# MagEnc.net
KiCad netlist of a schematic drawn in EAGLE
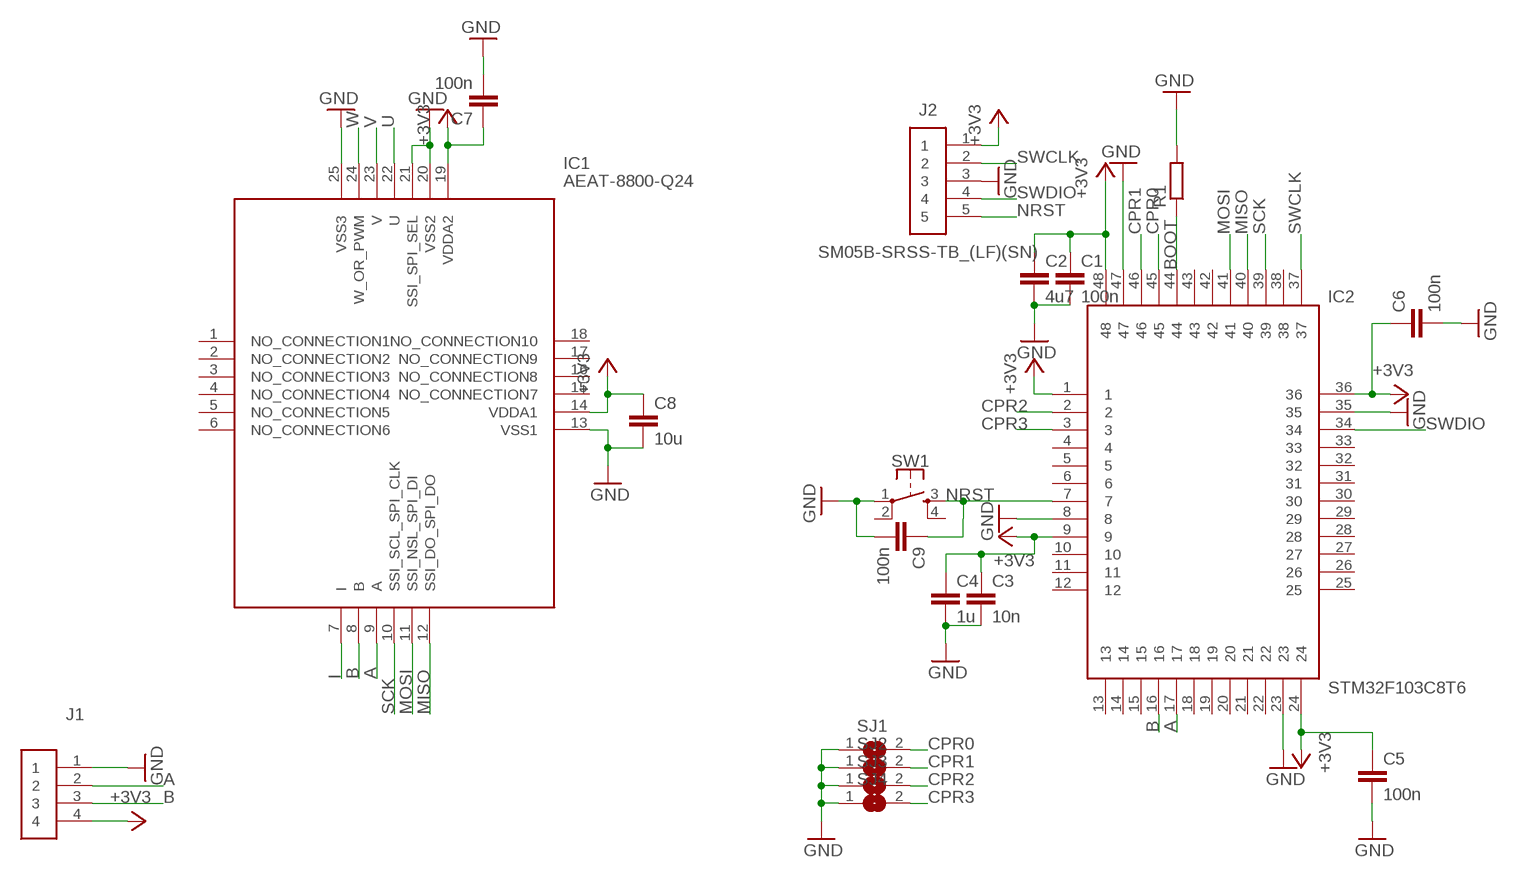
[diagram p0: schematic, sheet 1]

(export (version "E")
  (design (tool "Eeschema 10.0.6"))
  (components
    (comp (ref "C1")
      (value "100n")
      (footprint "eagle-import:C0402K")
      (libsource (lib "eagle-import") (part "C-EUC0402K"))
    )
    (comp (ref "C2")
      (value "4u7")
      (footprint "eagle-import:C0603K")
      (libsource (lib "eagle-import") (part "C-EUC0603K"))
    )
    (comp (ref "C3")
      (value "10n")
      (footprint "eagle-import:C0402K")
      (libsource (lib "eagle-import") (part "C-EUC0402K"))
    )
    (comp (ref "C4")
      (value "1u")
      (footprint "eagle-import:C0603K")
      (libsource (lib "eagle-import") (part "C-EUC0603K"))
    )
    (comp (ref "C5")
      (value "100n")
      (footprint "eagle-import:C0402K")
      (libsource (lib "eagle-import") (part "C-EUC0402K"))
    )
    (comp (ref "C6")
      (value "100n")
      (footprint "eagle-import:C0402K")
      (libsource (lib "eagle-import") (part "C-EUC0402K"))
    )
    (comp (ref "C7")
      (value "100n")
      (footprint "eagle-import:C0402K")
      (libsource (lib "eagle-import") (part "C-EUC0402K"))
    )
    (comp (ref "C8")
      (value "10u")
      (footprint "eagle-import:C0603K")
      (libsource (lib "eagle-import") (part "C-EUC0603K"))
    )
    (comp (ref "C9")
      (value "100n")
      (footprint "eagle-import:C0402K")
      (libsource (lib "eagle-import") (part "C-EUC0402K"))
    )
    (comp (ref "IC1")
      (value "AEAT-8800-Q24")
      (footprint "eagle-import:QFN65P500X500X90-25N")
      (libsource (lib "eagle-import") (part "AEAT-8800-Q24"))
    )
    (comp (ref "IC2")
      (value "STM32F103C8T6")
      (footprint "eagle-import:QFP50P900X900X160-48N")
      (libsource (lib "eagle-import") (part "STM32_LQFP48_7X7"))
    )
    (comp (ref "J1")
      (value "DF65-4P-1.7V(21)")
      (footprint "eagle-import:DF654P17V21")
      (fields (field (name "RS_PART_NUMBER") "8735161P"))
      (libsource (lib "eagle-import") (part "DF65-4P-1.7V(21)"))
    )
    (comp (ref "J2")
      (value "SM05B-SRSS-TB_(LF)(SN)")
      (footprint "eagle-import:SM05B-SRSS-TB")
      (fields (field (name "MANUFACTURER_PART_NUMBER") "SM05B-SRSS-TB(LF)(SN)"))
      (libsource (lib "eagle-import") (part "SM05B-SRSS-TB_(LF)(SN)"))
    )
    (comp (ref "R1")
      (value "R-EU_R0402")
      (footprint "eagle-import:R0402")
      (libsource (lib "eagle-import") (part "R-EU_R0402"))
    )
    (comp (ref "SJ1") (value "SJ") (footprint "eagle-import:SJ") (libsource (lib "eagle-import") (part "SJ")))
    (comp (ref "SJ2") (value "SJ") (footprint "eagle-import:SJ") (libsource (lib "eagle-import") (part "SJ")))
    (comp (ref "SJ3") (value "SJ") (footprint "eagle-import:SJ") (libsource (lib "eagle-import") (part "SJ")))
    (comp (ref "SJ4") (value "SJ") (footprint "eagle-import:SJ") (libsource (lib "eagle-import") (part "SJ")))
    (comp (ref "SW1")
      (value "SKRPACE010")
      (footprint "eagle-import:SMT(4.2X3.2)")
      (libsource (lib "eagle-import") (part "SKRPACE010"))
    )
  )
  (nets
    (net (code "1") (name "+3V3") (class "Default")
      (node (ref "C1") (pin "1") (pinfunction "1_1") (pintype "passive"))
      (node (ref "C2") (pin "1") (pinfunction "1_1") (pintype "passive"))
      (node (ref "C3") (pin "1") (pinfunction "1_1") (pintype "passive"))
      (node (ref "C4") (pin "1") (pinfunction "1_1") (pintype "passive"))
      (node (ref "C5") (pin "1") (pinfunction "1_1") (pintype "passive"))
      (node (ref "C6") (pin "1") (pinfunction "1_1") (pintype "passive"))
      (node (ref "C7") (pin "1") (pinfunction "1_1") (pintype "passive"))
      (node (ref "C8") (pin "1") (pinfunction "1_1") (pintype "passive"))
      (node (ref "IC1") (pin "14") (pinfunction "VDDA1_14") (pintype "bidirectional"))
      (node (ref "IC1") (pin "19") (pinfunction "VDDA2_19") (pintype "bidirectional"))
      (node (ref "IC2") (pin "1") (pinfunction "1_1") (pintype "bidirectional"))
      (node (ref "IC2") (pin "24") (pinfunction "24_24") (pintype "bidirectional"))
      (node (ref "IC2") (pin "36") (pinfunction "36_36") (pintype "bidirectional"))
      (node (ref "IC2") (pin "48") (pinfunction "48_48") (pintype "bidirectional"))
      (node (ref "IC2") (pin "9") (pinfunction "9_9") (pintype "bidirectional"))
      (node (ref "J1") (pin "4") (pinfunction "4_4") (pintype "input"))
      (node (ref "J2") (pin "1") (pinfunction "1_1") (pintype "passive"))
    )
    (net (code "2") (name "/A") (class "Default")
      (node (ref "IC1") (pin "9") (pinfunction "A_9") (pintype "bidirectional"))
      (node (ref "IC2") (pin "17") (pinfunction "17_17") (pintype "bidirectional"))
      (node (ref "J1") (pin "2") (pinfunction "2_2") (pintype "input"))
    )
    (net (code "3") (name "/B") (class "Default")
      (node (ref "IC1") (pin "8") (pinfunction "B_8") (pintype "bidirectional"))
      (node (ref "IC2") (pin "16") (pinfunction "16_16") (pintype "bidirectional"))
      (node (ref "J1") (pin "3") (pinfunction "3_3") (pintype "input"))
    )
    (net (code "4") (name "/BOOT") (class "Default")
      (node (ref "IC2") (pin "44") (pinfunction "44_44") (pintype "bidirectional"))
      (node (ref "R1") (pin "1") (pinfunction "1_1") (pintype "passive"))
    )
    (net (code "5") (name "/CPR0") (class "Default")
      (node (ref "IC2") (pin "45") (pinfunction "45_45") (pintype "bidirectional"))
      (node (ref "SJ1") (pin "2") (pinfunction "2_2") (pintype "passive"))
    )
    (net (code "6") (name "/CPR1") (class "Default")
      (node (ref "IC2") (pin "46") (pinfunction "46_46") (pintype "bidirectional"))
      (node (ref "SJ2") (pin "2") (pinfunction "2_2") (pintype "passive"))
    )
    (net (code "7") (name "/CPR2") (class "Default")
      (node (ref "IC2") (pin "2") (pinfunction "2_2") (pintype "bidirectional"))
      (node (ref "SJ3") (pin "2") (pinfunction "2_2") (pintype "passive"))
    )
    (net (code "8") (name "/CPR3") (class "Default")
      (node (ref "IC2") (pin "3") (pinfunction "3_3") (pintype "bidirectional"))
      (node (ref "SJ4") (pin "2") (pinfunction "2_2") (pintype "passive"))
    )
    (net (code "9") (name "/I") (class "Default")
      (node (ref "IC1") (pin "7") (pinfunction "I_7") (pintype "bidirectional"))
    )
    (net (code "10") (name "/MISO") (class "Default")
      (node (ref "IC1") (pin "12") (pinfunction "SSI_DO_SPI_DO_12") (pintype "bidirectional"))
      (node (ref "IC2") (pin "40") (pinfunction "40_40") (pintype "bidirectional"))
    )
    (net (code "11") (name "/MOSI") (class "Default")
      (node (ref "IC1") (pin "11") (pinfunction "SSI_NSL_SPI_DI_11") (pintype "bidirectional"))
      (node (ref "IC2") (pin "41") (pinfunction "41_41") (pintype "bidirectional"))
    )
    (net (code "12") (name "/NRST") (class "Default")
      (node (ref "C9") (pin "1") (pinfunction "1_1") (pintype "passive"))
      (node (ref "IC2") (pin "7") (pinfunction "7_7") (pintype "bidirectional"))
      (node (ref "J2") (pin "5") (pinfunction "5_5") (pintype "passive"))
      (node (ref "SW1") (pin "3") (pinfunction "3_3") (pintype "passive"))
    )
    (net (code "13") (name "/SCK") (class "Default")
      (node (ref "IC1") (pin "10") (pinfunction "SSI_SCL_SPI_CLK_10") (pintype "bidirectional"))
      (node (ref "IC2") (pin "39") (pinfunction "39_39") (pintype "bidirectional"))
    )
    (net (code "14") (name "/SWCLK") (class "Default")
      (node (ref "IC2") (pin "37") (pinfunction "37_37") (pintype "bidirectional"))
      (node (ref "J2") (pin "2") (pinfunction "2_2") (pintype "passive"))
    )
    (net (code "15") (name "/SWDIO") (class "Default")
      (node (ref "IC2") (pin "34") (pinfunction "34_34") (pintype "bidirectional"))
      (node (ref "J2") (pin "4") (pinfunction "4_4") (pintype "passive"))
    )
    (net (code "16") (name "/U") (class "Default")
      (node (ref "IC1") (pin "22") (pinfunction "U_22") (pintype "bidirectional"))
    )
    (net (code "17") (name "/V") (class "Default")
      (node (ref "IC1") (pin "23") (pinfunction "V_23") (pintype "bidirectional"))
    )
    (net (code "18") (name "/W") (class "Default")
      (node (ref "IC1") (pin "24") (pinfunction "W_OR_PWM_24") (pintype "bidirectional"))
    )
    (net (code "19") (name "GND") (class "Default")
      (node (ref "C1") (pin "2") (pinfunction "2_2") (pintype "passive"))
      (node (ref "C2") (pin "2") (pinfunction "2_2") (pintype "passive"))
      (node (ref "C3") (pin "2") (pinfunction "2_2") (pintype "passive"))
      (node (ref "C4") (pin "2") (pinfunction "2_2") (pintype "passive"))
      (node (ref "C5") (pin "2") (pinfunction "2_2") (pintype "passive"))
      (node (ref "C6") (pin "2") (pinfunction "2_2") (pintype "passive"))
      (node (ref "C7") (pin "2") (pinfunction "2_2") (pintype "passive"))
      (node (ref "C8") (pin "2") (pinfunction "2_2") (pintype "passive"))
      (node (ref "C9") (pin "2") (pinfunction "2_2") (pintype "passive"))
      (node (ref "IC1") (pin "13") (pinfunction "VSS1_13") (pintype "bidirectional"))
      (node (ref "IC1") (pin "20") (pinfunction "VSS2_20") (pintype "bidirectional"))
      (node (ref "IC1") (pin "21") (pinfunction "SSI_SPI_SEL_21") (pintype "bidirectional"))
      (node (ref "IC1") (pin "25") (pinfunction "VSS3_25") (pintype "bidirectional"))
      (node (ref "IC2") (pin "23") (pinfunction "23_23") (pintype "bidirectional"))
      (node (ref "IC2") (pin "35") (pinfunction "35_35") (pintype "bidirectional"))
      (node (ref "IC2") (pin "47") (pinfunction "47_47") (pintype "bidirectional"))
      (node (ref "IC2") (pin "8") (pinfunction "8_8") (pintype "bidirectional"))
      (node (ref "J1") (pin "1") (pinfunction "1_1") (pintype "input"))
      (node (ref "J2") (pin "3") (pinfunction "3_3") (pintype "passive"))
      (node (ref "R1") (pin "2") (pinfunction "2_2") (pintype "passive"))
      (node (ref "SJ1") (pin "1") (pinfunction "1_1") (pintype "passive"))
      (node (ref "SJ2") (pin "1") (pinfunction "1_1") (pintype "passive"))
      (node (ref "SJ3") (pin "1") (pinfunction "1_1") (pintype "passive"))
      (node (ref "SJ4") (pin "1") (pinfunction "1_1") (pintype "passive"))
      (node (ref "SW1") (pin "1") (pinfunction "1_1") (pintype "passive"))
    )
    (net (code "20") (name "unconnected-(IC1-NO_CONNECTION1-Pad1)") (class "Default")
      (node (ref "IC1") (pin "1") (pinfunction "NO_CONNECTION1_1") (pintype "bidirectional"))
    )
    (net (code "21") (name "unconnected-(IC1-NO_CONNECTION2-Pad2)") (class "Default")
      (node (ref "IC1") (pin "2") (pinfunction "NO_CONNECTION2_2") (pintype "bidirectional"))
    )
    (net (code "22") (name "unconnected-(IC1-NO_CONNECTION3-Pad3)") (class "Default")
      (node (ref "IC1") (pin "3") (pinfunction "NO_CONNECTION3_3") (pintype "bidirectional"))
    )
    (net (code "23") (name "unconnected-(IC1-NO_CONNECTION4-Pad4)") (class "Default")
      (node (ref "IC1") (pin "4") (pinfunction "NO_CONNECTION4_4") (pintype "bidirectional"))
    )
    (net (code "24") (name "unconnected-(IC1-NO_CONNECTION5-Pad5)") (class "Default")
      (node (ref "IC1") (pin "5") (pinfunction "NO_CONNECTION5_5") (pintype "bidirectional"))
    )
    (net (code "25") (name "unconnected-(IC1-NO_CONNECTION6-Pad6)") (class "Default")
      (node (ref "IC1") (pin "6") (pinfunction "NO_CONNECTION6_6") (pintype "bidirectional"))
    )
    (net (code "26") (name "unconnected-(IC1-NO_CONNECTION7-Pad15)") (class "Default")
      (node (ref "IC1") (pin "15") (pinfunction "NO_CONNECTION7_15") (pintype "bidirectional"))
    )
    (net (code "27") (name "unconnected-(IC1-NO_CONNECTION8-Pad16)") (class "Default")
      (node (ref "IC1") (pin "16") (pinfunction "NO_CONNECTION8_16") (pintype "bidirectional"))
    )
    (net (code "28") (name "unconnected-(IC1-NO_CONNECTION9-Pad17)") (class "Default")
      (node (ref "IC1") (pin "17") (pinfunction "NO_CONNECTION9_17") (pintype "bidirectional"))
    )
    (net (code "29") (name "unconnected-(IC1-NO_CONNECTION10-Pad18)") (class "Default")
      (node (ref "IC1") (pin "18") (pinfunction "NO_CONNECTION10_18") (pintype "bidirectional"))
    )
    (net (code "30") (name "unconnected-(IC2-Pad4)") (class "Default")
      (node (ref "IC2") (pin "4") (pinfunction "4_4") (pintype "bidirectional"))
    )
    (net (code "31") (name "unconnected-(IC2-Pad5)") (class "Default")
      (node (ref "IC2") (pin "5") (pinfunction "5_5") (pintype "bidirectional"))
    )
    (net (code "32") (name "unconnected-(IC2-Pad6)") (class "Default")
      (node (ref "IC2") (pin "6") (pinfunction "6_6") (pintype "bidirectional"))
    )
    (net (code "33") (name "unconnected-(IC2-Pad10)") (class "Default")
      (node (ref "IC2") (pin "10") (pinfunction "10_10") (pintype "bidirectional"))
    )
    (net (code "34") (name "unconnected-(IC2-Pad11)") (class "Default")
      (node (ref "IC2") (pin "11") (pinfunction "11_11") (pintype "bidirectional"))
    )
    (net (code "35") (name "unconnected-(IC2-Pad12)") (class "Default")
      (node (ref "IC2") (pin "12") (pinfunction "12_12") (pintype "bidirectional"))
    )
    (net (code "36") (name "unconnected-(IC2-Pad13)") (class "Default")
      (node (ref "IC2") (pin "13") (pinfunction "13_13") (pintype "bidirectional"))
    )
    (net (code "37") (name "unconnected-(IC2-Pad14)") (class "Default")
      (node (ref "IC2") (pin "14") (pinfunction "14_14") (pintype "bidirectional"))
    )
    (net (code "38") (name "unconnected-(IC2-Pad15)") (class "Default")
      (node (ref "IC2") (pin "15") (pinfunction "15_15") (pintype "bidirectional"))
    )
    (net (code "39") (name "unconnected-(IC2-Pad18)") (class "Default")
      (node (ref "IC2") (pin "18") (pinfunction "18_18") (pintype "bidirectional"))
    )
    (net (code "40") (name "unconnected-(IC2-Pad19)") (class "Default")
      (node (ref "IC2") (pin "19") (pinfunction "19_19") (pintype "bidirectional"))
    )
    (net (code "41") (name "unconnected-(IC2-Pad20)") (class "Default")
      (node (ref "IC2") (pin "20") (pinfunction "20_20") (pintype "bidirectional"))
    )
    (net (code "42") (name "unconnected-(IC2-Pad21)") (class "Default")
      (node (ref "IC2") (pin "21") (pinfunction "21_21") (pintype "bidirectional"))
    )
    (net (code "43") (name "unconnected-(IC2-Pad22)") (class "Default")
      (node (ref "IC2") (pin "22") (pinfunction "22_22") (pintype "bidirectional"))
    )
    (net (code "44") (name "unconnected-(IC2-Pad25)") (class "Default")
      (node (ref "IC2") (pin "25") (pinfunction "25_25") (pintype "bidirectional"))
    )
    (net (code "45") (name "unconnected-(IC2-Pad26)") (class "Default")
      (node (ref "IC2") (pin "26") (pinfunction "26_26") (pintype "bidirectional"))
    )
    (net (code "46") (name "unconnected-(IC2-Pad27)") (class "Default")
      (node (ref "IC2") (pin "27") (pinfunction "27_27") (pintype "bidirectional"))
    )
    (net (code "47") (name "unconnected-(IC2-Pad28)") (class "Default")
      (node (ref "IC2") (pin "28") (pinfunction "28_28") (pintype "bidirectional"))
    )
    (net (code "48") (name "unconnected-(IC2-Pad29)") (class "Default")
      (node (ref "IC2") (pin "29") (pinfunction "29_29") (pintype "bidirectional"))
    )
    (net (code "49") (name "unconnected-(IC2-Pad30)") (class "Default")
      (node (ref "IC2") (pin "30") (pinfunction "30_30") (pintype "bidirectional"))
    )
    (net (code "50") (name "unconnected-(IC2-Pad31)") (class "Default")
      (node (ref "IC2") (pin "31") (pinfunction "31_31") (pintype "bidirectional"))
    )
    (net (code "51") (name "unconnected-(IC2-Pad32)") (class "Default")
      (node (ref "IC2") (pin "32") (pinfunction "32_32") (pintype "bidirectional"))
    )
    (net (code "52") (name "unconnected-(IC2-Pad33)") (class "Default")
      (node (ref "IC2") (pin "33") (pinfunction "33_33") (pintype "bidirectional"))
    )
    (net (code "53") (name "unconnected-(IC2-Pad38)") (class "Default")
      (node (ref "IC2") (pin "38") (pinfunction "38_38") (pintype "bidirectional"))
    )
    (net (code "54") (name "unconnected-(IC2-Pad42)") (class "Default")
      (node (ref "IC2") (pin "42") (pinfunction "42_42") (pintype "bidirectional"))
    )
    (net (code "55") (name "unconnected-(IC2-Pad43)") (class "Default")
      (node (ref "IC2") (pin "43") (pinfunction "43_43") (pintype "bidirectional"))
    )
    (net (code "56") (name "unconnected-(SW1-Pad2)") (class "Default")
      (node (ref "SW1") (pin "2") (pinfunction "2_2") (pintype "passive"))
    )
    (net (code "57") (name "unconnected-(SW1-Pad4)") (class "Default")
      (node (ref "SW1") (pin "4") (pinfunction "4_4") (pintype "passive"))
    )
  )
)
